# valhalla-pump-panel.net
KiCad netlist of a schematic drawn in EAGLE
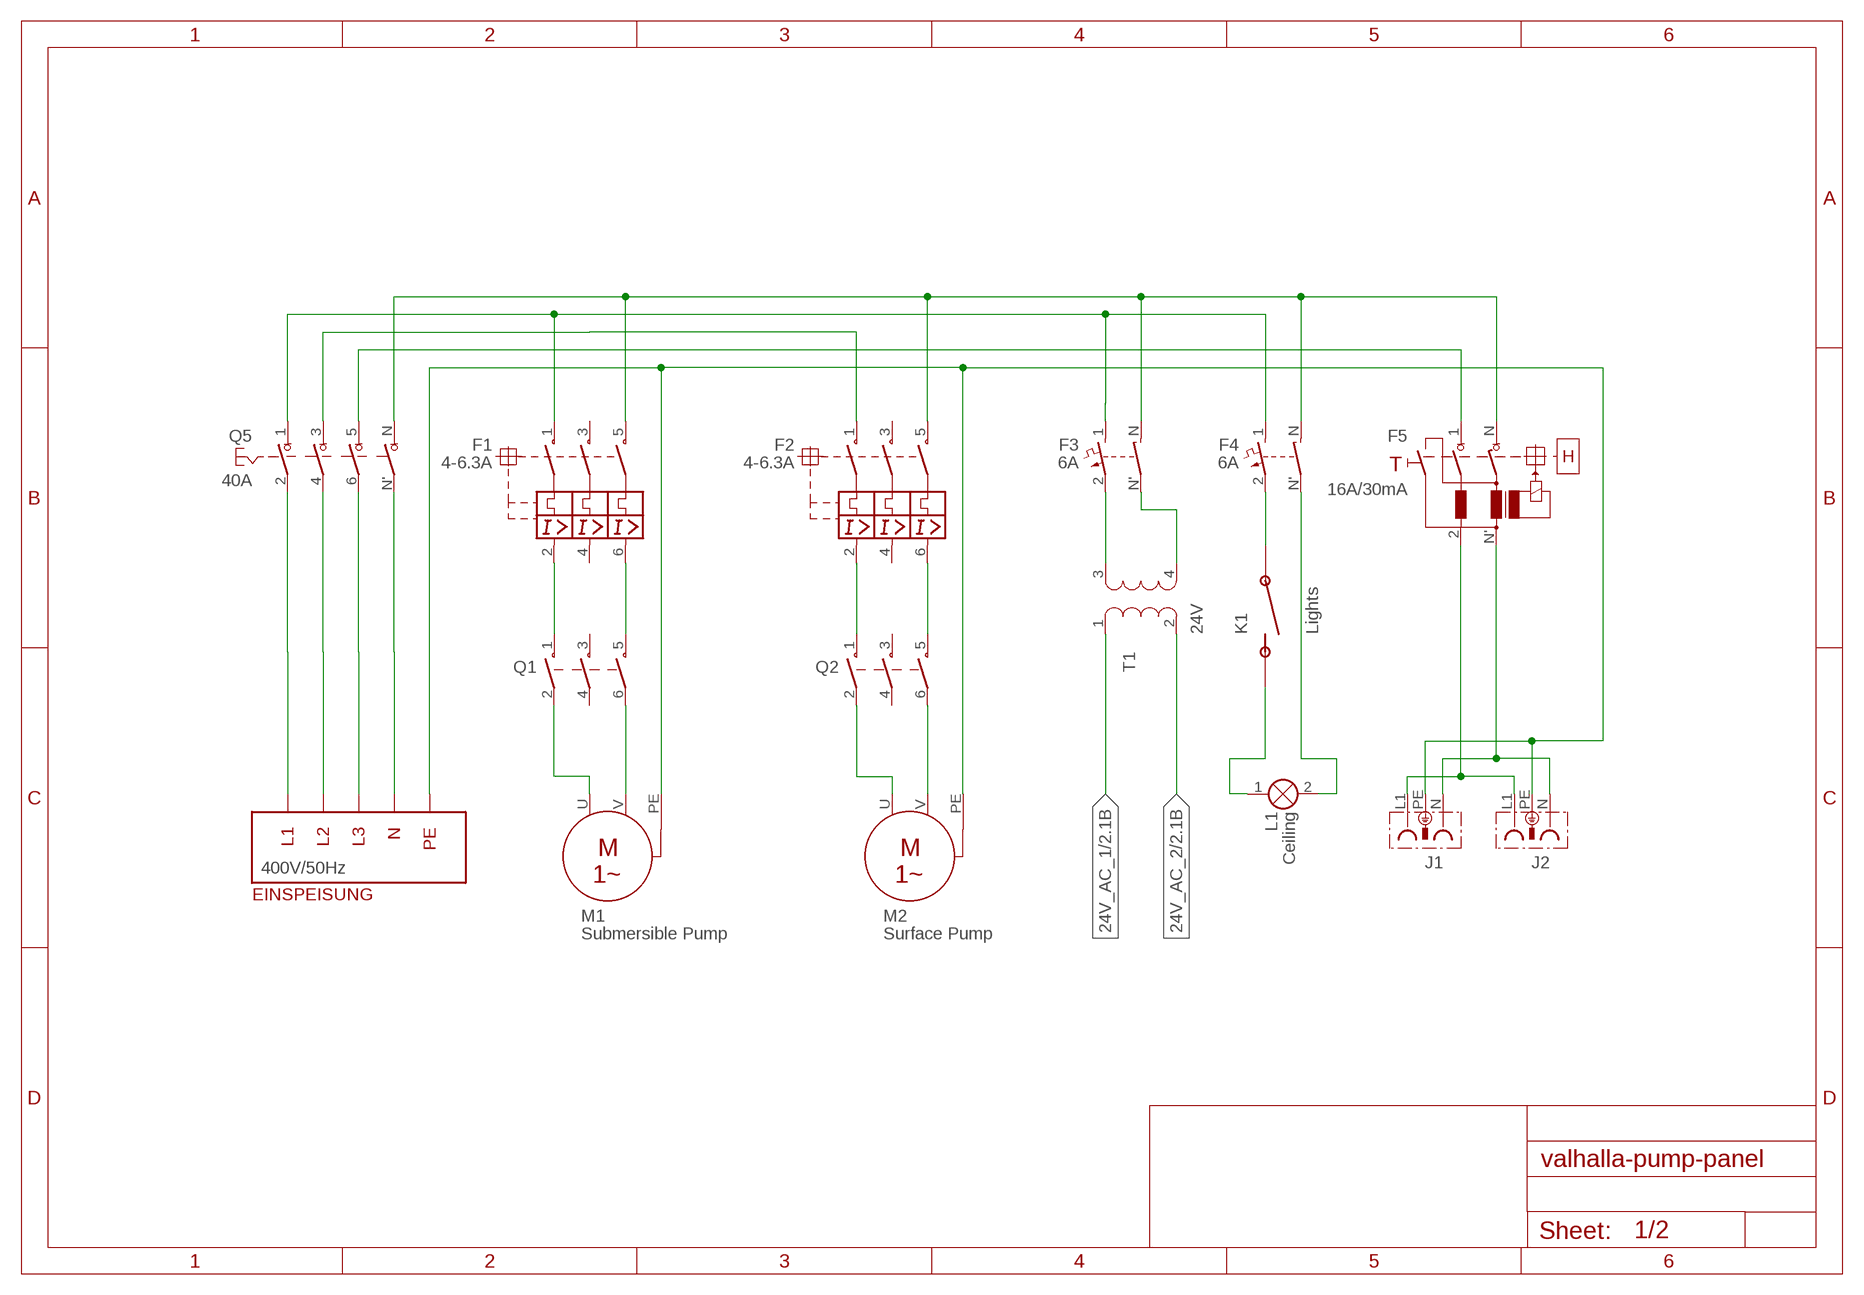
[diagram p0: schematic, sheet 1]
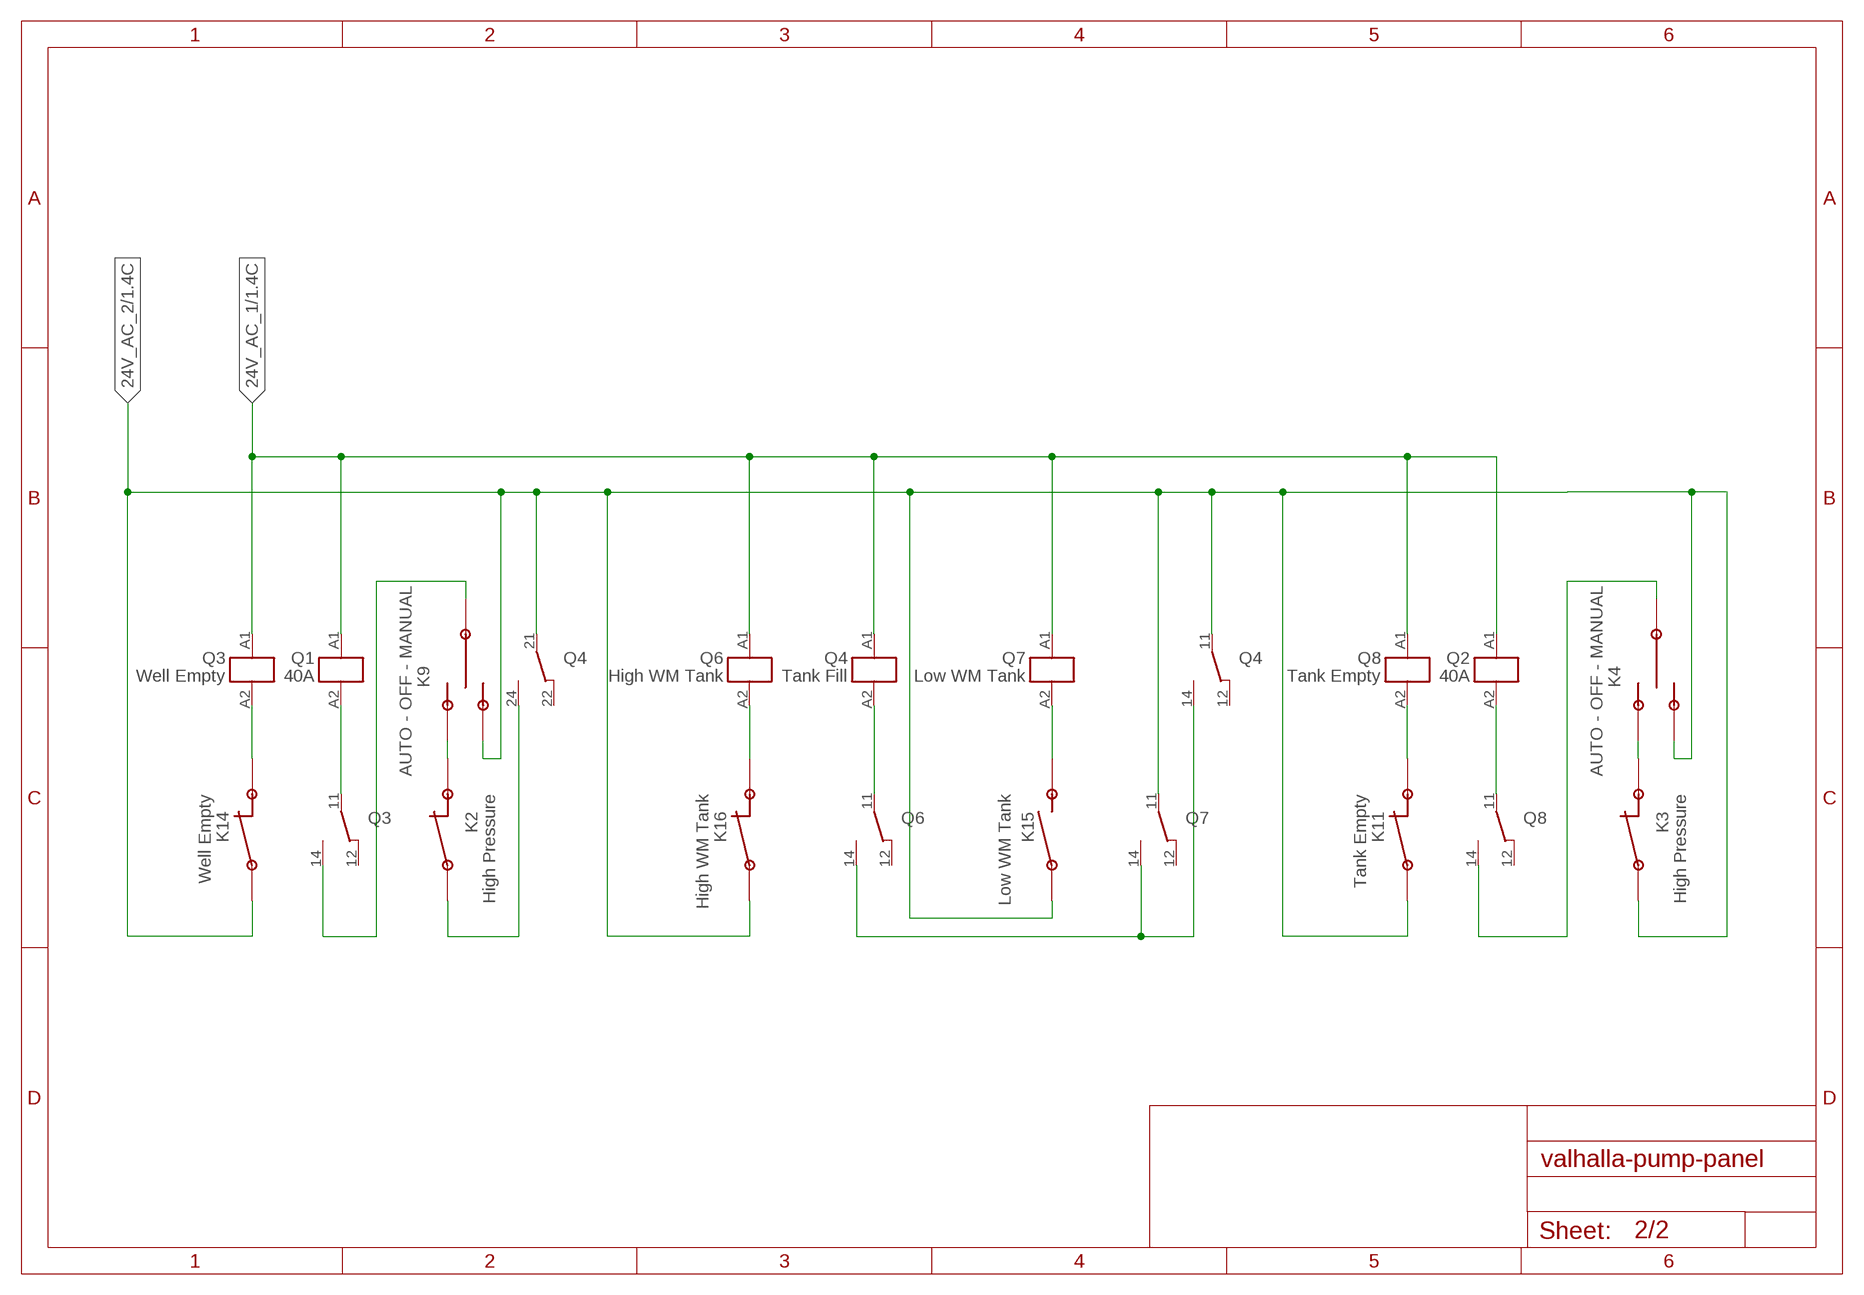
[diagram p1: schematic, sheet 2]

(export (version "E")
  (design (tool "Eeschema 10.0.6"))
  (components
    (comp (ref "F1")
      (value "4-6.3A")
      (footprint "eagle-import:MOTORSCHUTZSCHALTER_3-POL_THERM_MAG_HANDBETAETIGT_HILFSKONTAKTE")
      (libsource (lib "eagle-import") (part "MOTORSCHUTZSCHALTER_3-POL_THERM_MAG_HANDBETAETIGT_HILFSKONTAKTE"))
    )
    (comp (ref "F2")
      (value "4-6.3A")
      (footprint "eagle-import:MOTORSCHUTZSCHALTER_3-POL_THERM_MAG_HANDBETAETIGT_HILFSKONTAKTE")
      (libsource (lib "eagle-import") (part "MOTORSCHUTZSCHALTER_3-POL_THERM_MAG_HANDBETAETIGT_HILFSKONTAKTE"))
    )
    (comp (ref "F3")
      (value "6A")
      (footprint "eagle-import:LEITUNGSSCHUTZSCHALTER_2-POL")
      (libsource (lib "eagle-import") (part "LEITUNGSSCHUTZSCHALTER_2-POL"))
    )
    (comp (ref "F4")
      (value "6A")
      (footprint "eagle-import:LEITUNGSSCHUTZSCHALTER_2-POL")
      (libsource (lib "eagle-import") (part "LEITUNGSSCHUTZSCHALTER_2-POL"))
    )
    (comp (ref "F5")
      (value "16A/30mA")
      (footprint "eagle-import:FEHLER-STROM-SCHUTZSCHALTER_2-POL")
      (libsource (lib "eagle-import") (part "FEHLER-STROM-SCHUTZSCHALTER_2-POL"))
    )
    (comp (ref "J1")
      (value "STECKDOSE")
      (footprint "eagle-import:STECKDOSE")
      (libsource (lib "eagle-import") (part "STECKDOSE"))
    )
    (comp (ref "J2")
      (value "STECKDOSE")
      (footprint "eagle-import:STECKDOSE")
      (fields (field (name "SPICEPREFIX") "J"))
      (libsource (lib "eagle-import") (part "STECKDOSE"))
    )
    (comp (ref "L1")
      (value "Ceiling")
      (footprint "eagle-import:LAMPE")
      (libsource (lib "eagle-import") (part "SIGNALLAMPE"))
    )
    (comp (ref "M1")
      (value "Submersible Pump")
      (footprint "eagle-import:MOTOR_1-PHASEN")
      (libsource (lib "eagle-import") (part "MOTOR_1-PHASEN"))
    )
    (comp (ref "M2")
      (value "Surface Pump")
      (footprint "eagle-import:MOTOR_1-PHASEN")
      (libsource (lib "eagle-import") (part "MOTOR_1-PHASEN"))
    )
    (comp (ref "Q1")
      (value "40A")
      (footprint "eagle-import:HAUPTSCHUETZ_3-POL")
      (libsource (lib "eagle-import") (part "HAUPTSCHUETZ_3-POL"))
    )
    (comp (ref "Q2")
      (value "40A")
      (footprint "eagle-import:HAUPTSCHUETZ_3-POL")
      (libsource (lib "eagle-import") (part "HAUPTSCHUETZ_3-POL"))
    )
    (comp (ref "Q5")
      (value "40A")
      (footprint "eagle-import:LASTTRENNSCHALTER_4-POL")
      (libsource (lib "eagle-import") (part "LASTTRENNSCHALTER_4-POL"))
    )
    (comp (ref "T1")
      (value "TRANSFORMATOR")
      (footprint "eagle-import:TRANSFORMATOR")
      (fields (field (name "TYPE") "24V"))
      (libsource (lib "eagle-import") (part "TRANSFORMATOR"))
    )
    (comp (ref "Q3")
      (value "Well Empty")
      (footprint "eagle-import:RELAIS_2-POL-UM")
      (libsource (lib "eagle-import") (part "RELAIS_2-POL-UM"))
    )
    (comp (ref "Q4")
      (value "Tank Fill")
      (footprint "eagle-import:RELAIS_2-POL-UM")
      (libsource (lib "eagle-import") (part "RELAIS_2-POL-UM"))
    )
    (comp (ref "Q6")
      (value "High WM Tank")
      (footprint "eagle-import:RELAIS_2-POL-UM")
      (libsource (lib "eagle-import") (part "RELAIS_2-POL-UM"))
    )
    (comp (ref "Q7")
      (value "Low WM Tank")
      (footprint "eagle-import:RELAIS_2-POL-UM")
      (libsource (lib "eagle-import") (part "RELAIS_2-POL-UM"))
    )
    (comp (ref "Q8")
      (value "Tank Empty")
      (footprint "eagle-import:RELAIS_2-POL-UM")
      (libsource (lib "eagle-import") (part "RELAIS_2-POL-UM"))
    )
  )
  (nets
    (net (code "1") (name "24V_AC_1") (class "Default")
      (node (ref "Q1") (pin "A1") (pinfunction "A1_A1") (pintype "input"))
      (node (ref "Q2") (pin "A1") (pinfunction "A1_A1") (pintype "input"))
      (node (ref "Q3") (pin "A1") (pinfunction "A1_A1") (pintype "input"))
      (node (ref "Q4") (pin "A1") (pinfunction "A1_A1") (pintype "input"))
      (node (ref "Q6") (pin "A1") (pinfunction "A1_A1") (pintype "input"))
      (node (ref "Q7") (pin "A1") (pinfunction "A1_A1") (pintype "input"))
      (node (ref "Q8") (pin "A1") (pinfunction "A1_A1") (pintype "input"))
      (node (ref "T1") (pin "1") (pinfunction "1_1") (pintype "passive"))
    )
    (net (code "2") (name "24V_AC_2") (class "Default")
      (node (ref "Q4") (pin "11") (pinfunction "1_11") (pintype "passive"))
      (node (ref "Q4") (pin "21") (pinfunction "1_21") (pintype "passive"))
      (node (ref "Q7") (pin "11") (pinfunction "1_11") (pintype "passive"))
      (node (ref "T1") (pin "2") (pinfunction "2_2") (pintype "passive"))
    )
    (net (code "3") (name "Net-(F1-Pad1)") (class "Default")
      (node (ref "F1") (pin "1") (pinfunction "1_1") (pintype "passive"))
      (node (ref "F3") (pin "1") (pinfunction "1_1") (pintype "passive"))
      (node (ref "F4") (pin "1") (pinfunction "1_1") (pintype "passive"))
      (node (ref "Q5") (pin "1") (pinfunction "1_1") (pintype "input"))
    )
    (net (code "4") (name "Net-(F1-Pad2)") (class "Default")
      (node (ref "F1") (pin "2") (pinfunction "2_2") (pintype "passive"))
      (node (ref "Q1") (pin "1") (pinfunction "1_1") (pintype "passive"))
    )
    (net (code "5") (name "Net-(F1-Pad6)") (class "Default")
      (node (ref "F1") (pin "6") (pinfunction "6_6") (pintype "passive"))
      (node (ref "Q1") (pin "5") (pinfunction "5_5") (pintype "passive"))
    )
    (net (code "6") (name "Net-(F2-Pad1)") (class "Default")
      (node (ref "F2") (pin "1") (pinfunction "1_1") (pintype "passive"))
      (node (ref "Q5") (pin "3") (pinfunction "3_3") (pintype "input"))
    )
    (net (code "7") (name "Net-(F2-Pad2)") (class "Default")
      (node (ref "F2") (pin "2") (pinfunction "2_2") (pintype "passive"))
      (node (ref "Q2") (pin "1") (pinfunction "1_1") (pintype "passive"))
    )
    (net (code "8") (name "Net-(F2-Pad6)") (class "Default")
      (node (ref "F2") (pin "6") (pinfunction "6_6") (pintype "passive"))
      (node (ref "Q2") (pin "5") (pinfunction "5_5") (pintype "passive"))
    )
    (net (code "9") (name "Net-(F3-N-PadN')") (class "Default")
      (node (ref "F3") (pin "N'") (pinfunction "N_N'") (pintype "passive"))
      (node (ref "T1") (pin "4") (pinfunction "4_4") (pintype "passive"))
    )
    (net (code "10") (name "Net-(F3-Pad2)") (class "Default")
      (node (ref "F3") (pin "2") (pinfunction "2_2") (pintype "passive"))
      (node (ref "T1") (pin "3") (pinfunction "3_3") (pintype "passive"))
    )
    (net (code "11") (name "Net-(F5-Pad1)") (class "Default")
      (node (ref "F5") (pin "1") (pinfunction "1_1") (pintype "passive"))
      (node (ref "Q5") (pin "5") (pinfunction "5_5") (pintype "input"))
    )
    (net (code "12") (name "Net-(F5-Pad2)") (class "Default")
      (node (ref "F5") (pin "2") (pinfunction "2_2") (pintype "passive"))
      (node (ref "J1") (pin "L1") (pinfunction "L1_L1") (pintype "passive"))
      (node (ref "J2") (pin "L1") (pinfunction "L1_L1") (pintype "passive"))
    )
    (net (code "13") (name "Net-(F5-PadN')") (class "Default")
      (node (ref "F5") (pin "N'") (pinfunction "N'_N'") (pintype "passive"))
      (node (ref "J1") (pin "N") (pinfunction "N_N") (pintype "passive"))
      (node (ref "J2") (pin "N") (pinfunction "N_N") (pintype "passive"))
    )
    (net (code "14") (name "Net-(J1-PadPE)") (class "Default")
      (node (ref "J1") (pin "PE") (pinfunction "PE_PE") (pintype "passive"))
      (node (ref "J2") (pin "PE") (pinfunction "PE_PE") (pintype "passive"))
      (node (ref "M1") (pin "PE") (pinfunction "PE_PE") (pintype "passive"))
      (node (ref "M2") (pin "PE") (pinfunction "PE_PE") (pintype "passive"))
    )
    (net (code "15") (name "Net-(L1-X2)") (class "Default")
      (node (ref "F4") (pin "N'") (pinfunction "N_N'") (pintype "passive"))
      (node (ref "L1") (pin "2") (pinfunction "X2_2") (pintype "passive"))
    )
    (net (code "16") (name "Net-(M1-PadU)") (class "Default")
      (node (ref "M1") (pin "U") (pinfunction "U_U") (pintype "passive"))
      (node (ref "Q1") (pin "2") (pinfunction "2_2") (pintype "passive"))
    )
    (net (code "17") (name "Net-(M1-PadV)") (class "Default")
      (node (ref "M1") (pin "V") (pinfunction "V_V") (pintype "passive"))
      (node (ref "Q1") (pin "6") (pinfunction "6_6") (pintype "passive"))
    )
    (net (code "18") (name "Net-(M2-PadU)") (class "Default")
      (node (ref "M2") (pin "U") (pinfunction "U_U") (pintype "passive"))
      (node (ref "Q2") (pin "2") (pinfunction "2_2") (pintype "passive"))
    )
    (net (code "19") (name "Net-(M2-PadV)") (class "Default")
      (node (ref "M2") (pin "V") (pinfunction "V_V") (pintype "passive"))
      (node (ref "Q2") (pin "6") (pinfunction "6_6") (pintype "passive"))
    )
    (net (code "20") (name "Net-(Q3A-1)") (class "Default")
      (node (ref "Q1") (pin "A2") (pinfunction "A2_A2") (pintype "input"))
      (node (ref "Q3") (pin "11") (pinfunction "1_11") (pintype "passive"))
    )
    (net (code "21") (name "Net-(Q3A-4)") (class "Default")
      (node (ref "Q3") (pin "14") (pinfunction "4_14") (pintype "passive"))
    )
    (net (code "22") (name "Net-(Q4A-4)") (class "Default")
      (node (ref "Q4") (pin "14") (pinfunction "4_14") (pintype "passive"))
      (node (ref "Q6") (pin "14") (pinfunction "4_14") (pintype "passive"))
      (node (ref "Q7") (pin "14") (pinfunction "4_14") (pintype "passive"))
    )
    (net (code "23") (name "Net-(Q5-7)") (class "Default")
      (node (ref "F1") (pin "5") (pinfunction "5_5") (pintype "passive"))
      (node (ref "F2") (pin "5") (pinfunction "5_5") (pintype "passive"))
      (node (ref "F3") (pin "N") (pinfunction "N_N") (pintype "passive"))
      (node (ref "F4") (pin "N") (pinfunction "N_N") (pintype "passive"))
      (node (ref "F5") (pin "N") (pinfunction "N_N") (pintype "passive"))
      (node (ref "Q5") (pin "N") (pinfunction "7_N") (pintype "input"))
    )
    (net (code "24") (name "Net-(Q5-8)") (class "Default")
      (node (ref "Q5") (pin "N'") (pinfunction "8_N'") (pintype "input"))
    )
    (net (code "25") (name "Net-(Q5-Pad2)") (class "Default")
      (node (ref "Q5") (pin "2") (pinfunction "2_2") (pintype "input"))
    )
    (net (code "26") (name "Net-(Q5-Pad4)") (class "Default")
      (node (ref "Q5") (pin "4") (pinfunction "4_4") (pintype "input"))
    )
    (net (code "27") (name "Net-(Q5-Pad6)") (class "Default")
      (node (ref "Q5") (pin "6") (pinfunction "6_6") (pintype "input"))
    )
    (net (code "28") (name "Net-(Q6A-1)") (class "Default")
      (node (ref "Q4") (pin "A2") (pinfunction "A2_A2") (pintype "input"))
      (node (ref "Q6") (pin "11") (pinfunction "1_11") (pintype "passive"))
    )
    (net (code "29") (name "Net-(Q8A-1)") (class "Default")
      (node (ref "Q2") (pin "A2") (pinfunction "A2_A2") (pintype "input"))
      (node (ref "Q8") (pin "11") (pinfunction "1_11") (pintype "passive"))
    )
    (net (code "30") (name "Net-(Q8A-4)") (class "Default")
      (node (ref "Q8") (pin "14") (pinfunction "4_14") (pintype "passive"))
    )
    (net (code "31") (name "P$1") (class "Default")
      (node (ref "F4") (pin "2") (pinfunction "2_2") (pintype "passive"))
      (node (ref "Q4") (pin "24") (pinfunction "4_24") (pintype "passive"))
    )
    (net (code "32") (name "P$2") (class "Default")
      (node (ref "L1") (pin "1") (pinfunction "X1_1") (pintype "passive"))
      (node (ref "Q3") (pin "A2") (pinfunction "A2_A2") (pintype "input"))
      (node (ref "Q6") (pin "A2") (pinfunction "A2_A2") (pintype "input"))
      (node (ref "Q7") (pin "A2") (pinfunction "A2_A2") (pintype "input"))
      (node (ref "Q8") (pin "A2") (pinfunction "A2_A2") (pintype "input"))
    )
    (net (code "33") (name "unconnected-(F1-Pad3)") (class "Default")
      (node (ref "F1") (pin "3") (pinfunction "3_3") (pintype "passive"))
    )
    (net (code "34") (name "unconnected-(F1-Pad4)") (class "Default")
      (node (ref "F1") (pin "4") (pinfunction "4_4") (pintype "passive"))
    )
    (net (code "35") (name "unconnected-(F2-Pad3)") (class "Default")
      (node (ref "F2") (pin "3") (pinfunction "3_3") (pintype "passive"))
    )
    (net (code "36") (name "unconnected-(F2-Pad4)") (class "Default")
      (node (ref "F2") (pin "4") (pinfunction "4_4") (pintype "passive"))
    )
    (net (code "37") (name "unconnected-(Q1-Pad3)") (class "Default")
      (node (ref "Q1") (pin "3") (pinfunction "3_3") (pintype "passive"))
    )
    (net (code "38") (name "unconnected-(Q1-Pad4)") (class "Default")
      (node (ref "Q1") (pin "4") (pinfunction "4_4") (pintype "passive"))
    )
    (net (code "39") (name "unconnected-(Q2-Pad3)") (class "Default")
      (node (ref "Q2") (pin "3") (pinfunction "3_3") (pintype "passive"))
    )
    (net (code "40") (name "unconnected-(Q2-Pad4)") (class "Default")
      (node (ref "Q2") (pin "4") (pinfunction "4_4") (pintype "passive"))
    )
    (net (code "41") (name "unconnected-(Q3A-2-Pad12)") (class "Default")
      (node (ref "Q3") (pin "12") (pinfunction "2_12") (pintype "passive"))
    )
    (net (code "42") (name "unconnected-(Q4A-2-Pad12)") (class "Default")
      (node (ref "Q4") (pin "12") (pinfunction "2_12") (pintype "passive"))
    )
    (net (code "43") (name "unconnected-(Q4B-2-Pad22)") (class "Default")
      (node (ref "Q4") (pin "22") (pinfunction "2_22") (pintype "passive"))
    )
    (net (code "44") (name "unconnected-(Q6A-2-Pad12)") (class "Default")
      (node (ref "Q6") (pin "12") (pinfunction "2_12") (pintype "passive"))
    )
    (net (code "45") (name "unconnected-(Q7A-2-Pad12)") (class "Default")
      (node (ref "Q7") (pin "12") (pinfunction "2_12") (pintype "passive"))
    )
    (net (code "46") (name "unconnected-(Q8A-2-Pad12)") (class "Default")
      (node (ref "Q8") (pin "12") (pinfunction "2_12") (pintype "passive"))
    )
  )
)
